# main2.net
KiCad netlist of a schematic drawn in EAGLE
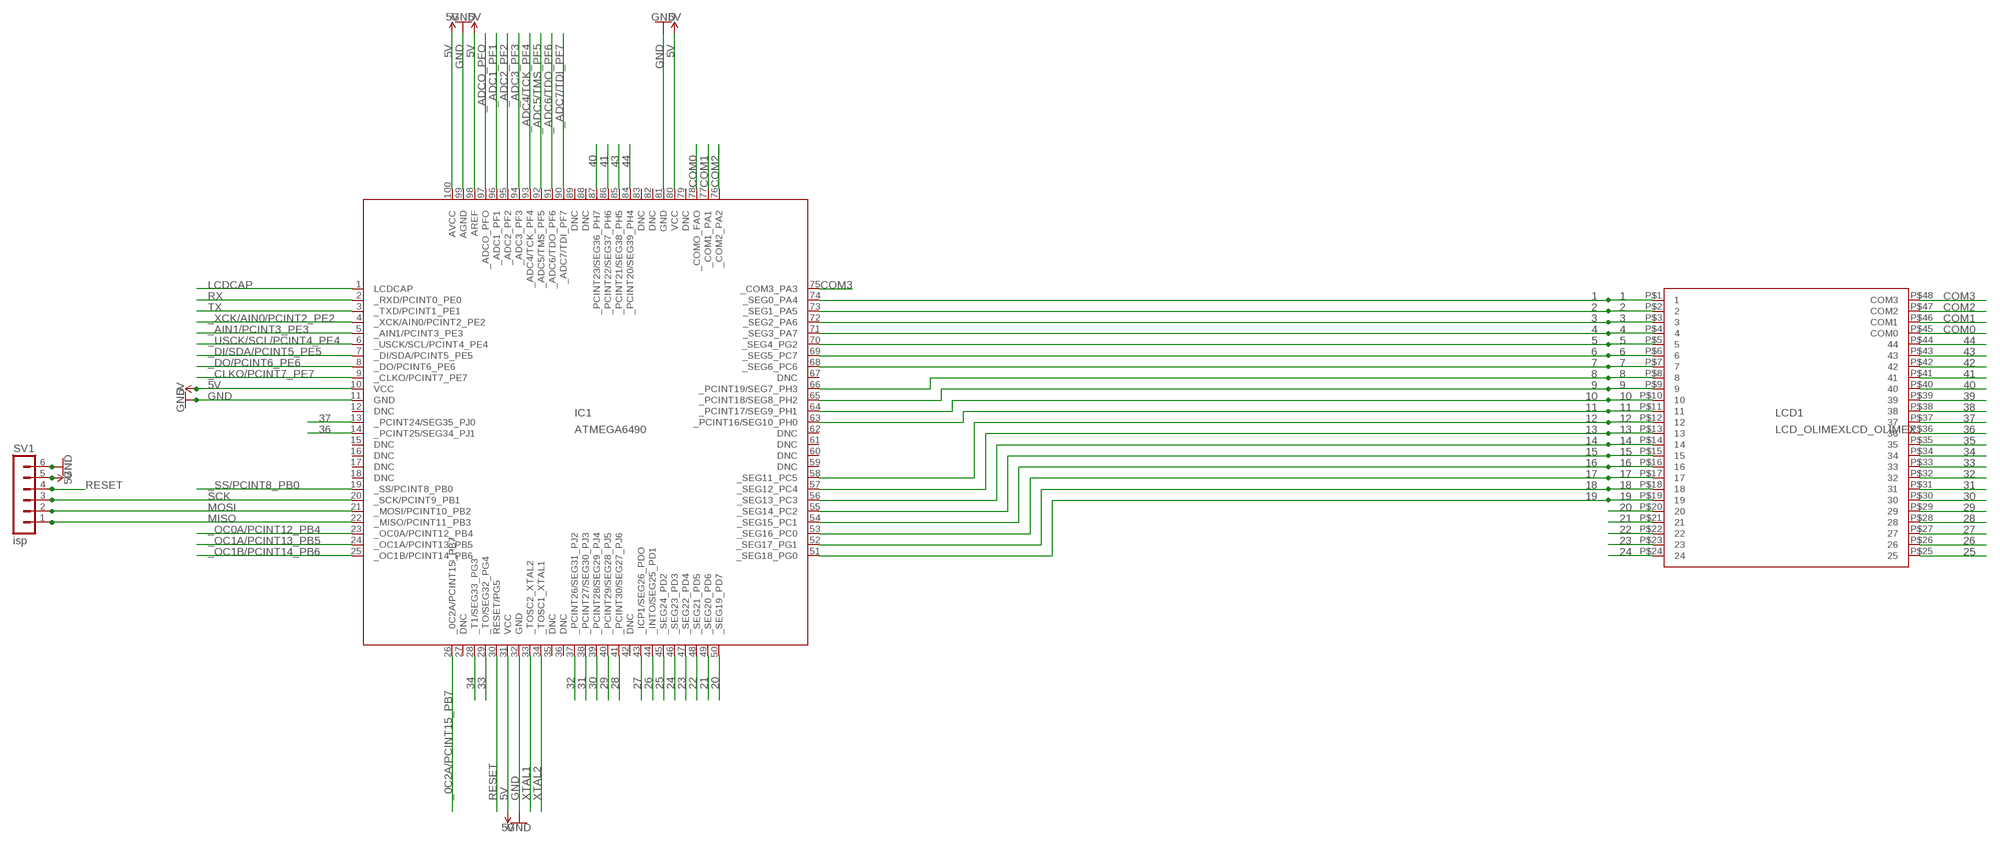
[diagram p0: schematic, sheet 1]

(export (version "E")
  (design (tool "Eeschema 10.0.6"))
  (components
    (comp (ref "IC1")
      (value "ATMEGA6490")
      (footprint "eagle-import:TQFP100")
      (libsource (lib "eagle-import") (part "ATMEGA6490"))
    )
    (comp (ref "LCD1")
      (value "LCD_OLIMEXLCD_OLIMEX")
      (footprint "eagle-import:LCD_OLIMEX")
      (libsource (lib "eagle-import") (part "LCD_OLIMEXLCD_OLIMEX"))
    )
    (comp (ref "SV1")
      (value "isp")
      (footprint "eagle-import:MA06-1")
      (libsource (lib "eagle-import") (part "MA06-1"))
    )
  )
  (nets
    (net (code "1") (name "/1") (class "Default")
      (node (ref "IC1") (pin "74") (pinfunction "_SEG0_PA4_74") (pintype "bidirectional"))
      (node (ref "LCD1") (pin "P$1") (pinfunction "1_P$1") (pintype "bidirectional"))
    )
    (net (code "2") (name "/2") (class "Default")
      (node (ref "IC1") (pin "73") (pinfunction "_SEG1_PA5_73") (pintype "bidirectional"))
      (node (ref "LCD1") (pin "P$2") (pinfunction "2_P$2") (pintype "bidirectional"))
    )
    (net (code "3") (name "/3") (class "Default")
      (node (ref "IC1") (pin "72") (pinfunction "_SEG2_PA6_72") (pintype "bidirectional"))
      (node (ref "LCD1") (pin "P$3") (pinfunction "3_P$3") (pintype "bidirectional"))
    )
    (net (code "4") (name "/4") (class "Default")
      (node (ref "IC1") (pin "71") (pinfunction "_SEG3_PA7_71") (pintype "bidirectional"))
      (node (ref "LCD1") (pin "P$4") (pinfunction "4_P$4") (pintype "bidirectional"))
    )
    (net (code "5") (name "/5") (class "Default")
      (node (ref "IC1") (pin "70") (pinfunction "_SEG4_PG2_70") (pintype "bidirectional"))
      (node (ref "LCD1") (pin "P$5") (pinfunction "5_P$5") (pintype "bidirectional"))
    )
    (net (code "6") (name "/6") (class "Default")
      (node (ref "IC1") (pin "69") (pinfunction "_SEG5_PC7_69") (pintype "bidirectional"))
      (node (ref "LCD1") (pin "P$6") (pinfunction "6_P$6") (pintype "bidirectional"))
    )
    (net (code "7") (name "/7") (class "Default")
      (node (ref "IC1") (pin "68") (pinfunction "_SEG6_PC6_68") (pintype "bidirectional"))
      (node (ref "LCD1") (pin "P$7") (pinfunction "7_P$7") (pintype "bidirectional"))
    )
    (net (code "8") (name "/8") (class "Default")
      (node (ref "IC1") (pin "66") (pinfunction "_PCINT19/SEG7_PH3_66") (pintype "bidirectional"))
      (node (ref "LCD1") (pin "P$8") (pinfunction "8_P$8") (pintype "bidirectional"))
    )
    (net (code "9") (name "/9") (class "Default")
      (node (ref "IC1") (pin "65") (pinfunction "_PCINT18/SEG8_PH2_65") (pintype "bidirectional"))
      (node (ref "LCD1") (pin "P$9") (pinfunction "9_P$9") (pintype "bidirectional"))
    )
    (net (code "10") (name "/10") (class "Default")
      (node (ref "IC1") (pin "64") (pinfunction "_PCINT17/SEG9_PH1_64") (pintype "bidirectional"))
      (node (ref "LCD1") (pin "P$10") (pinfunction "10_P$10") (pintype "bidirectional"))
    )
    (net (code "11") (name "/11") (class "Default")
      (node (ref "IC1") (pin "63") (pinfunction "_PCINT16/SEG10_PH0_63") (pintype "bidirectional"))
      (node (ref "LCD1") (pin "P$11") (pinfunction "11_P$11") (pintype "bidirectional"))
    )
    (net (code "12") (name "/12") (class "Default")
      (node (ref "IC1") (pin "58") (pinfunction "_SEG11_PC5_58") (pintype "bidirectional"))
      (node (ref "LCD1") (pin "P$12") (pinfunction "12_P$12") (pintype "bidirectional"))
    )
    (net (code "13") (name "/13") (class "Default")
      (node (ref "IC1") (pin "57") (pinfunction "_SEG12_PC4_57") (pintype "bidirectional"))
      (node (ref "LCD1") (pin "P$13") (pinfunction "13_P$13") (pintype "bidirectional"))
    )
    (net (code "14") (name "/14") (class "Default")
      (node (ref "IC1") (pin "56") (pinfunction "_SEG13_PC3_56") (pintype "bidirectional"))
      (node (ref "LCD1") (pin "P$14") (pinfunction "14_P$14") (pintype "bidirectional"))
    )
    (net (code "15") (name "/15") (class "Default")
      (node (ref "IC1") (pin "55") (pinfunction "_SEG14_PC2_55") (pintype "bidirectional"))
      (node (ref "LCD1") (pin "P$15") (pinfunction "15_P$15") (pintype "bidirectional"))
    )
    (net (code "16") (name "/16") (class "Default")
      (node (ref "IC1") (pin "54") (pinfunction "_SEG15_PC1_54") (pintype "bidirectional"))
      (node (ref "LCD1") (pin "P$16") (pinfunction "16_P$16") (pintype "bidirectional"))
    )
    (net (code "17") (name "/17") (class "Default")
      (node (ref "IC1") (pin "53") (pinfunction "_SEG16_PC0_53") (pintype "bidirectional"))
      (node (ref "LCD1") (pin "P$17") (pinfunction "17_P$17") (pintype "bidirectional"))
    )
    (net (code "18") (name "/18") (class "Default")
      (node (ref "IC1") (pin "52") (pinfunction "_SEG17_PG1_52") (pintype "bidirectional"))
      (node (ref "LCD1") (pin "P$18") (pinfunction "18_P$18") (pintype "bidirectional"))
    )
    (net (code "19") (name "/19") (class "Default")
      (node (ref "IC1") (pin "51") (pinfunction "_SEG18_PG0_51") (pintype "bidirectional"))
      (node (ref "LCD1") (pin "P$19") (pinfunction "19_P$19") (pintype "bidirectional"))
    )
    (net (code "20") (name "/20") (class "Default")
      (node (ref "IC1") (pin "50") (pinfunction "_SEG19_PD7_50") (pintype "bidirectional"))
      (node (ref "LCD1") (pin "P$20") (pinfunction "20_P$20") (pintype "bidirectional"))
    )
    (net (code "21") (name "/21") (class "Default")
      (node (ref "IC1") (pin "49") (pinfunction "_SEG20_PD6_49") (pintype "bidirectional"))
      (node (ref "LCD1") (pin "P$21") (pinfunction "21_P$21") (pintype "bidirectional"))
    )
    (net (code "22") (name "/22") (class "Default")
      (node (ref "IC1") (pin "48") (pinfunction "_SEG21_PD5_48") (pintype "bidirectional"))
      (node (ref "LCD1") (pin "P$22") (pinfunction "22_P$22") (pintype "bidirectional"))
    )
    (net (code "23") (name "/23") (class "Default")
      (node (ref "IC1") (pin "47") (pinfunction "_SEG22_PD4_47") (pintype "bidirectional"))
      (node (ref "LCD1") (pin "P$23") (pinfunction "23_P$23") (pintype "bidirectional"))
    )
    (net (code "24") (name "/24") (class "Default")
      (node (ref "IC1") (pin "46") (pinfunction "_SEG23_PD3_46") (pintype "bidirectional"))
      (node (ref "LCD1") (pin "P$24") (pinfunction "24_P$24") (pintype "bidirectional"))
    )
    (net (code "25") (name "/25") (class "Default")
      (node (ref "IC1") (pin "45") (pinfunction "_SEG24_PD2_45") (pintype "bidirectional"))
      (node (ref "LCD1") (pin "P$25") (pinfunction "25_P$25") (pintype "bidirectional"))
    )
    (net (code "26") (name "/26") (class "Default")
      (node (ref "IC1") (pin "44") (pinfunction "_INTO/SEG25_PD1_44") (pintype "bidirectional"))
      (node (ref "LCD1") (pin "P$26") (pinfunction "26_P$26") (pintype "bidirectional"))
    )
    (net (code "27") (name "/27") (class "Default")
      (node (ref "IC1") (pin "43") (pinfunction "_ICP1/SEG26_PDO_43") (pintype "bidirectional"))
      (node (ref "LCD1") (pin "P$27") (pinfunction "27_P$27") (pintype "bidirectional"))
    )
    (net (code "28") (name "/28") (class "Default")
      (node (ref "IC1") (pin "41") (pinfunction "_PCINT30/SEG27_PJ6_41") (pintype "bidirectional"))
      (node (ref "LCD1") (pin "P$28") (pinfunction "28_P$28") (pintype "bidirectional"))
    )
    (net (code "29") (name "/29") (class "Default")
      (node (ref "IC1") (pin "40") (pinfunction "_PCINT29/SEG28_PJ5_40") (pintype "bidirectional"))
      (node (ref "LCD1") (pin "P$29") (pinfunction "29_P$29") (pintype "bidirectional"))
    )
    (net (code "30") (name "/30") (class "Default")
      (node (ref "IC1") (pin "39") (pinfunction "_PCINT28/SEG29_PJ4_39") (pintype "bidirectional"))
      (node (ref "LCD1") (pin "P$30") (pinfunction "30_P$30") (pintype "bidirectional"))
    )
    (net (code "31") (name "/31") (class "Default")
      (node (ref "IC1") (pin "38") (pinfunction "_PCINT27/SEG30_PJ3_38") (pintype "bidirectional"))
      (node (ref "LCD1") (pin "P$31") (pinfunction "31_P$31") (pintype "bidirectional"))
    )
    (net (code "32") (name "/32") (class "Default")
      (node (ref "IC1") (pin "37") (pinfunction "_PCINT26/SEG31_PJ2_37") (pintype "bidirectional"))
      (node (ref "LCD1") (pin "P$32") (pinfunction "32_P$32") (pintype "bidirectional"))
    )
    (net (code "33") (name "/33") (class "Default")
      (node (ref "IC1") (pin "29") (pinfunction "_TO/SEG32_PG4_29") (pintype "bidirectional"))
      (node (ref "LCD1") (pin "P$33") (pinfunction "33_P$33") (pintype "bidirectional"))
    )
    (net (code "34") (name "/34") (class "Default")
      (node (ref "IC1") (pin "28") (pinfunction "_T1/SEG33_PG3_28") (pintype "bidirectional"))
      (node (ref "LCD1") (pin "P$34") (pinfunction "34_P$34") (pintype "bidirectional"))
    )
    (net (code "35") (name "/35") (class "Default")
      (node (ref "LCD1") (pin "P$35") (pinfunction "35_P$35") (pintype "bidirectional"))
    )
    (net (code "36") (name "/36") (class "Default")
      (node (ref "IC1") (pin "14") (pinfunction "_PCINT25/SEG34_PJ1_14") (pintype "bidirectional"))
      (node (ref "LCD1") (pin "P$36") (pinfunction "36_P$36") (pintype "bidirectional"))
    )
    (net (code "37") (name "/37") (class "Default")
      (node (ref "IC1") (pin "13") (pinfunction "_PCINT24/SEG35_PJ0_13") (pintype "bidirectional"))
      (node (ref "LCD1") (pin "P$37") (pinfunction "37_P$37") (pintype "bidirectional"))
    )
    (net (code "38") (name "/38") (class "Default")
      (node (ref "LCD1") (pin "P$38") (pinfunction "38_P$38") (pintype "bidirectional"))
    )
    (net (code "39") (name "/39") (class "Default")
      (node (ref "LCD1") (pin "P$39") (pinfunction "39_P$39") (pintype "bidirectional"))
    )
    (net (code "40") (name "/40") (class "Default")
      (node (ref "IC1") (pin "87") (pinfunction "_PCINT23/SEG36_PH7_87") (pintype "bidirectional"))
      (node (ref "LCD1") (pin "P$40") (pinfunction "40_P$40") (pintype "bidirectional"))
    )
    (net (code "41") (name "/41") (class "Default")
      (node (ref "IC1") (pin "86") (pinfunction "_PCINT22/SEG37_PH6_86") (pintype "bidirectional"))
      (node (ref "LCD1") (pin "P$41") (pinfunction "41_P$41") (pintype "bidirectional"))
    )
    (net (code "42") (name "/42") (class "Default")
      (node (ref "LCD1") (pin "P$42") (pinfunction "42_P$42") (pintype "bidirectional"))
    )
    (net (code "43") (name "/43") (class "Default")
      (node (ref "IC1") (pin "85") (pinfunction "_PCINT21/SEG38_PH5_85") (pintype "bidirectional"))
      (node (ref "LCD1") (pin "P$43") (pinfunction "43_P$43") (pintype "bidirectional"))
    )
    (net (code "44") (name "/44") (class "Default")
      (node (ref "IC1") (pin "84") (pinfunction "_PCINT20/SEG39_PH4_84") (pintype "bidirectional"))
      (node (ref "LCD1") (pin "P$44") (pinfunction "44_P$44") (pintype "bidirectional"))
    )
    (net (code "45") (name "/COM0") (class "Default")
      (node (ref "IC1") (pin "78") (pinfunction "_COMO_FAO_78") (pintype "bidirectional"))
      (node (ref "LCD1") (pin "P$45") (pinfunction "COM0_P$45") (pintype "bidirectional"))
    )
    (net (code "46") (name "/COM1") (class "Default")
      (node (ref "IC1") (pin "77") (pinfunction "_COM1_PA1_77") (pintype "bidirectional"))
      (node (ref "LCD1") (pin "P$46") (pinfunction "COM1_P$46") (pintype "bidirectional"))
    )
    (net (code "47") (name "/COM2") (class "Default")
      (node (ref "IC1") (pin "76") (pinfunction "_COM2_PA2_76") (pintype "bidirectional"))
      (node (ref "LCD1") (pin "P$47") (pinfunction "COM2_P$47") (pintype "bidirectional"))
    )
    (net (code "48") (name "/COM3") (class "Default")
      (node (ref "IC1") (pin "75") (pinfunction "_COM3_PA3_75") (pintype "bidirectional"))
      (node (ref "LCD1") (pin "P$48") (pinfunction "COM3_P$48") (pintype "bidirectional"))
    )
    (net (code "49") (name "/LCDCAP") (class "Default")
      (node (ref "IC1") (pin "1") (pinfunction "LCDCAP_1") (pintype "bidirectional"))
    )
    (net (code "50") (name "/MISO") (class "Default")
      (node (ref "IC1") (pin "22") (pinfunction "_MISO/PCINT11_PB3_22") (pintype "bidirectional"))
      (node (ref "SV1") (pin "1") (pinfunction "1_1") (pintype "passive"))
    )
    (net (code "51") (name "/MOSI") (class "Default")
      (node (ref "IC1") (pin "21") (pinfunction "_MOSI/PCINT10_PB2_21") (pintype "bidirectional"))
      (node (ref "SV1") (pin "2") (pinfunction "2_2") (pintype "passive"))
    )
    (net (code "52") (name "/RESET") (class "Default")
      (node (ref "IC1") (pin "30") (pinfunction "RESET/PG5_30") (pintype "bidirectional"))
      (node (ref "SV1") (pin "4") (pinfunction "4_4") (pintype "passive"))
    )
    (net (code "53") (name "/RX") (class "Default")
      (node (ref "IC1") (pin "2") (pinfunction "_RXD/PCINT0_PE0_2") (pintype "bidirectional"))
    )
    (net (code "54") (name "/SCK") (class "Default")
      (node (ref "IC1") (pin "20") (pinfunction "_SCK/PCINT9_PB1_20") (pintype "bidirectional"))
      (node (ref "SV1") (pin "3") (pinfunction "3_3") (pintype "passive"))
    )
    (net (code "55") (name "/TX") (class "Default")
      (node (ref "IC1") (pin "3") (pinfunction "_TXD/PCINT1_PE1_3") (pintype "bidirectional"))
    )
    (net (code "56") (name "/XTAL1") (class "Default")
      (node (ref "IC1") (pin "33") (pinfunction "_TOSC2_XTAL2_33") (pintype "bidirectional"))
    )
    (net (code "57") (name "/XTAL2") (class "Default")
      (node (ref "IC1") (pin "34") (pinfunction "_TOSC1_XTAL1_34") (pintype "bidirectional"))
    )
    (net (code "58") (name "/_0C2A{slash}PCINT15_PB7") (class "Default")
      (node (ref "IC1") (pin "26") (pinfunction "_0C2A/PCINT15_PB7_26") (pintype "bidirectional"))
    )
    (net (code "59") (name "/_ADC1_PF1") (class "Default")
      (node (ref "IC1") (pin "96") (pinfunction "_ADC1_PF1_96") (pintype "bidirectional"))
    )
    (net (code "60") (name "/_ADC2_PF2") (class "Default")
      (node (ref "IC1") (pin "95") (pinfunction "_ADC2_PF2_95") (pintype "bidirectional"))
    )
    (net (code "61") (name "/_ADC3_PF3") (class "Default")
      (node (ref "IC1") (pin "94") (pinfunction "_ADC3_PF3_94") (pintype "bidirectional"))
    )
    (net (code "62") (name "/_ADC4{slash}TCK_PF4") (class "Default")
      (node (ref "IC1") (pin "93") (pinfunction "_ADC4/TCK_PF4_93") (pintype "bidirectional"))
    )
    (net (code "63") (name "/_ADC5{slash}TMS_PF5") (class "Default")
      (node (ref "IC1") (pin "92") (pinfunction "_ADC5/TMS_PF5_92") (pintype "bidirectional"))
    )
    (net (code "64") (name "/_ADC6{slash}TDO_PF6") (class "Default")
      (node (ref "IC1") (pin "91") (pinfunction "_ADC6/TDO_PF6_91") (pintype "bidirectional"))
    )
    (net (code "65") (name "/_ADC7{slash}TDI_PF7") (class "Default")
      (node (ref "IC1") (pin "90") (pinfunction "_ADC7/TDI_PF7_90") (pintype "bidirectional"))
    )
    (net (code "66") (name "/_ADCO_PFO") (class "Default")
      (node (ref "IC1") (pin "97") (pinfunction "_ADCO_PFO_97") (pintype "bidirectional"))
    )
    (net (code "67") (name "/_AIN1{slash}PCINT3_PE3") (class "Default")
      (node (ref "IC1") (pin "5") (pinfunction "_AIN1/PCINT3_PE3_5") (pintype "bidirectional"))
    )
    (net (code "68") (name "/_CLKO{slash}PCINT7_PE7") (class "Default")
      (node (ref "IC1") (pin "9") (pinfunction "_CLKO/PCINT7_PE7_9") (pintype "bidirectional"))
    )
    (net (code "69") (name "/_DI{slash}SDA{slash}PCINT5_PE5") (class "Default")
      (node (ref "IC1") (pin "7") (pinfunction "_DI/SDA/PCINT5_PE5_7") (pintype "bidirectional"))
    )
    (net (code "70") (name "/_DO{slash}PCINT6_PE6") (class "Default")
      (node (ref "IC1") (pin "8") (pinfunction "_DO/PCINT6_PE6_8") (pintype "bidirectional"))
    )
    (net (code "71") (name "/_OC0A{slash}PCINT12_PB4") (class "Default")
      (node (ref "IC1") (pin "23") (pinfunction "_OC0A/PCINT12_PB4_23") (pintype "bidirectional"))
    )
    (net (code "72") (name "/_OC1A{slash}PCINT13_PB5") (class "Default")
      (node (ref "IC1") (pin "24") (pinfunction "_OC1A/PCINT13_PB5_24") (pintype "bidirectional"))
    )
    (net (code "73") (name "/_OC1B{slash}PCINT14_PB6") (class "Default")
      (node (ref "IC1") (pin "25") (pinfunction "_OC1B/PCINT14_PB6_25") (pintype "bidirectional"))
    )
    (net (code "74") (name "/_SS{slash}PCINT8_PB0") (class "Default")
      (node (ref "IC1") (pin "19") (pinfunction "_SS/PCINT8_PB0_19") (pintype "bidirectional"))
    )
    (net (code "75") (name "/_USCK{slash}SCL{slash}PCINT4_PE4") (class "Default")
      (node (ref "IC1") (pin "6") (pinfunction "_USCK/SCL/PCINT4_PE4_6") (pintype "bidirectional"))
    )
    (net (code "76") (name "/_XCK{slash}AIN0{slash}PCINT2_PE2") (class "Default")
      (node (ref "IC1") (pin "4") (pinfunction "_XCK/AIN0/PCINT2_PE2_4") (pintype "bidirectional"))
    )
    (net (code "77") (name "5V") (class "Default")
      (node (ref "IC1") (pin "10") (pinfunction "VCC_10") (pintype "bidirectional"))
      (node (ref "IC1") (pin "100") (pinfunction "AVCC_100") (pintype "bidirectional"))
      (node (ref "IC1") (pin "31") (pinfunction "VCC_31") (pintype "bidirectional"))
      (node (ref "IC1") (pin "80") (pinfunction "VCC_80") (pintype "bidirectional"))
      (node (ref "IC1") (pin "98") (pinfunction "AREF_98") (pintype "bidirectional"))
      (node (ref "SV1") (pin "5") (pinfunction "5_5") (pintype "passive"))
    )
    (net (code "78") (name "GND") (class "Default")
      (node (ref "IC1") (pin "11") (pinfunction "GND_11") (pintype "bidirectional"))
      (node (ref "IC1") (pin "32") (pinfunction "GND_32") (pintype "bidirectional"))
      (node (ref "IC1") (pin "81") (pinfunction "GND_81") (pintype "bidirectional"))
      (node (ref "IC1") (pin "99") (pinfunction "AGND_99") (pintype "bidirectional"))
      (node (ref "SV1") (pin "6") (pinfunction "6_6") (pintype "passive"))
    )
    (net (code "79") (name "unconnected-(IC1-DNC-Pad12)") (class "Default")
      (node (ref "IC1") (pin "12") (pinfunction "DNC_12") (pintype "bidirectional"))
    )
    (net (code "80") (name "unconnected-(IC1-DNC-Pad15)") (class "Default")
      (node (ref "IC1") (pin "15") (pinfunction "DNC_15") (pintype "bidirectional"))
    )
    (net (code "81") (name "unconnected-(IC1-DNC-Pad16)") (class "Default")
      (node (ref "IC1") (pin "16") (pinfunction "DNC_16") (pintype "bidirectional"))
    )
    (net (code "82") (name "unconnected-(IC1-DNC-Pad17)") (class "Default")
      (node (ref "IC1") (pin "17") (pinfunction "DNC_17") (pintype "bidirectional"))
    )
    (net (code "83") (name "unconnected-(IC1-DNC-Pad18)") (class "Default")
      (node (ref "IC1") (pin "18") (pinfunction "DNC_18") (pintype "bidirectional"))
    )
    (net (code "84") (name "unconnected-(IC1-DNC-Pad27)") (class "Default")
      (node (ref "IC1") (pin "27") (pinfunction "DNC_27") (pintype "bidirectional"))
    )
    (net (code "85") (name "unconnected-(IC1-DNC-Pad35)") (class "Default")
      (node (ref "IC1") (pin "35") (pinfunction "DNC_35") (pintype "bidirectional"))
    )
    (net (code "86") (name "unconnected-(IC1-DNC-Pad36)") (class "Default")
      (node (ref "IC1") (pin "36") (pinfunction "DNC_36") (pintype "bidirectional"))
    )
    (net (code "87") (name "unconnected-(IC1-DNC-Pad42)") (class "Default")
      (node (ref "IC1") (pin "42") (pinfunction "DNC_42") (pintype "bidirectional"))
    )
    (net (code "88") (name "unconnected-(IC1-DNC-Pad59)") (class "Default")
      (node (ref "IC1") (pin "59") (pinfunction "DNC_59") (pintype "bidirectional"))
    )
    (net (code "89") (name "unconnected-(IC1-DNC-Pad60)") (class "Default")
      (node (ref "IC1") (pin "60") (pinfunction "DNC_60") (pintype "bidirectional"))
    )
    (net (code "90") (name "unconnected-(IC1-DNC-Pad61)") (class "Default")
      (node (ref "IC1") (pin "61") (pinfunction "DNC_61") (pintype "bidirectional"))
    )
    (net (code "91") (name "unconnected-(IC1-DNC-Pad62)") (class "Default")
      (node (ref "IC1") (pin "62") (pinfunction "DNC_62") (pintype "bidirectional"))
    )
    (net (code "92") (name "unconnected-(IC1-DNC-Pad67)") (class "Default")
      (node (ref "IC1") (pin "67") (pinfunction "DNC_67") (pintype "bidirectional"))
    )
    (net (code "93") (name "unconnected-(IC1-DNC-Pad79)") (class "Default")
      (node (ref "IC1") (pin "79") (pinfunction "DNC_79") (pintype "bidirectional"))
    )
    (net (code "94") (name "unconnected-(IC1-DNC-Pad82)") (class "Default")
      (node (ref "IC1") (pin "82") (pinfunction "DNC_82") (pintype "bidirectional"))
    )
    (net (code "95") (name "unconnected-(IC1-DNC-Pad83)") (class "Default")
      (node (ref "IC1") (pin "83") (pinfunction "DNC_83") (pintype "bidirectional"))
    )
    (net (code "96") (name "unconnected-(IC1-DNC-Pad88)") (class "Default")
      (node (ref "IC1") (pin "88") (pinfunction "DNC_88") (pintype "bidirectional"))
    )
    (net (code "97") (name "unconnected-(IC1-DNC-Pad89)") (class "Default")
      (node (ref "IC1") (pin "89") (pinfunction "DNC_89") (pintype "bidirectional"))
    )
  )
)
